# schematic.net
KiCad netlist of a schematic drawn in EAGLE
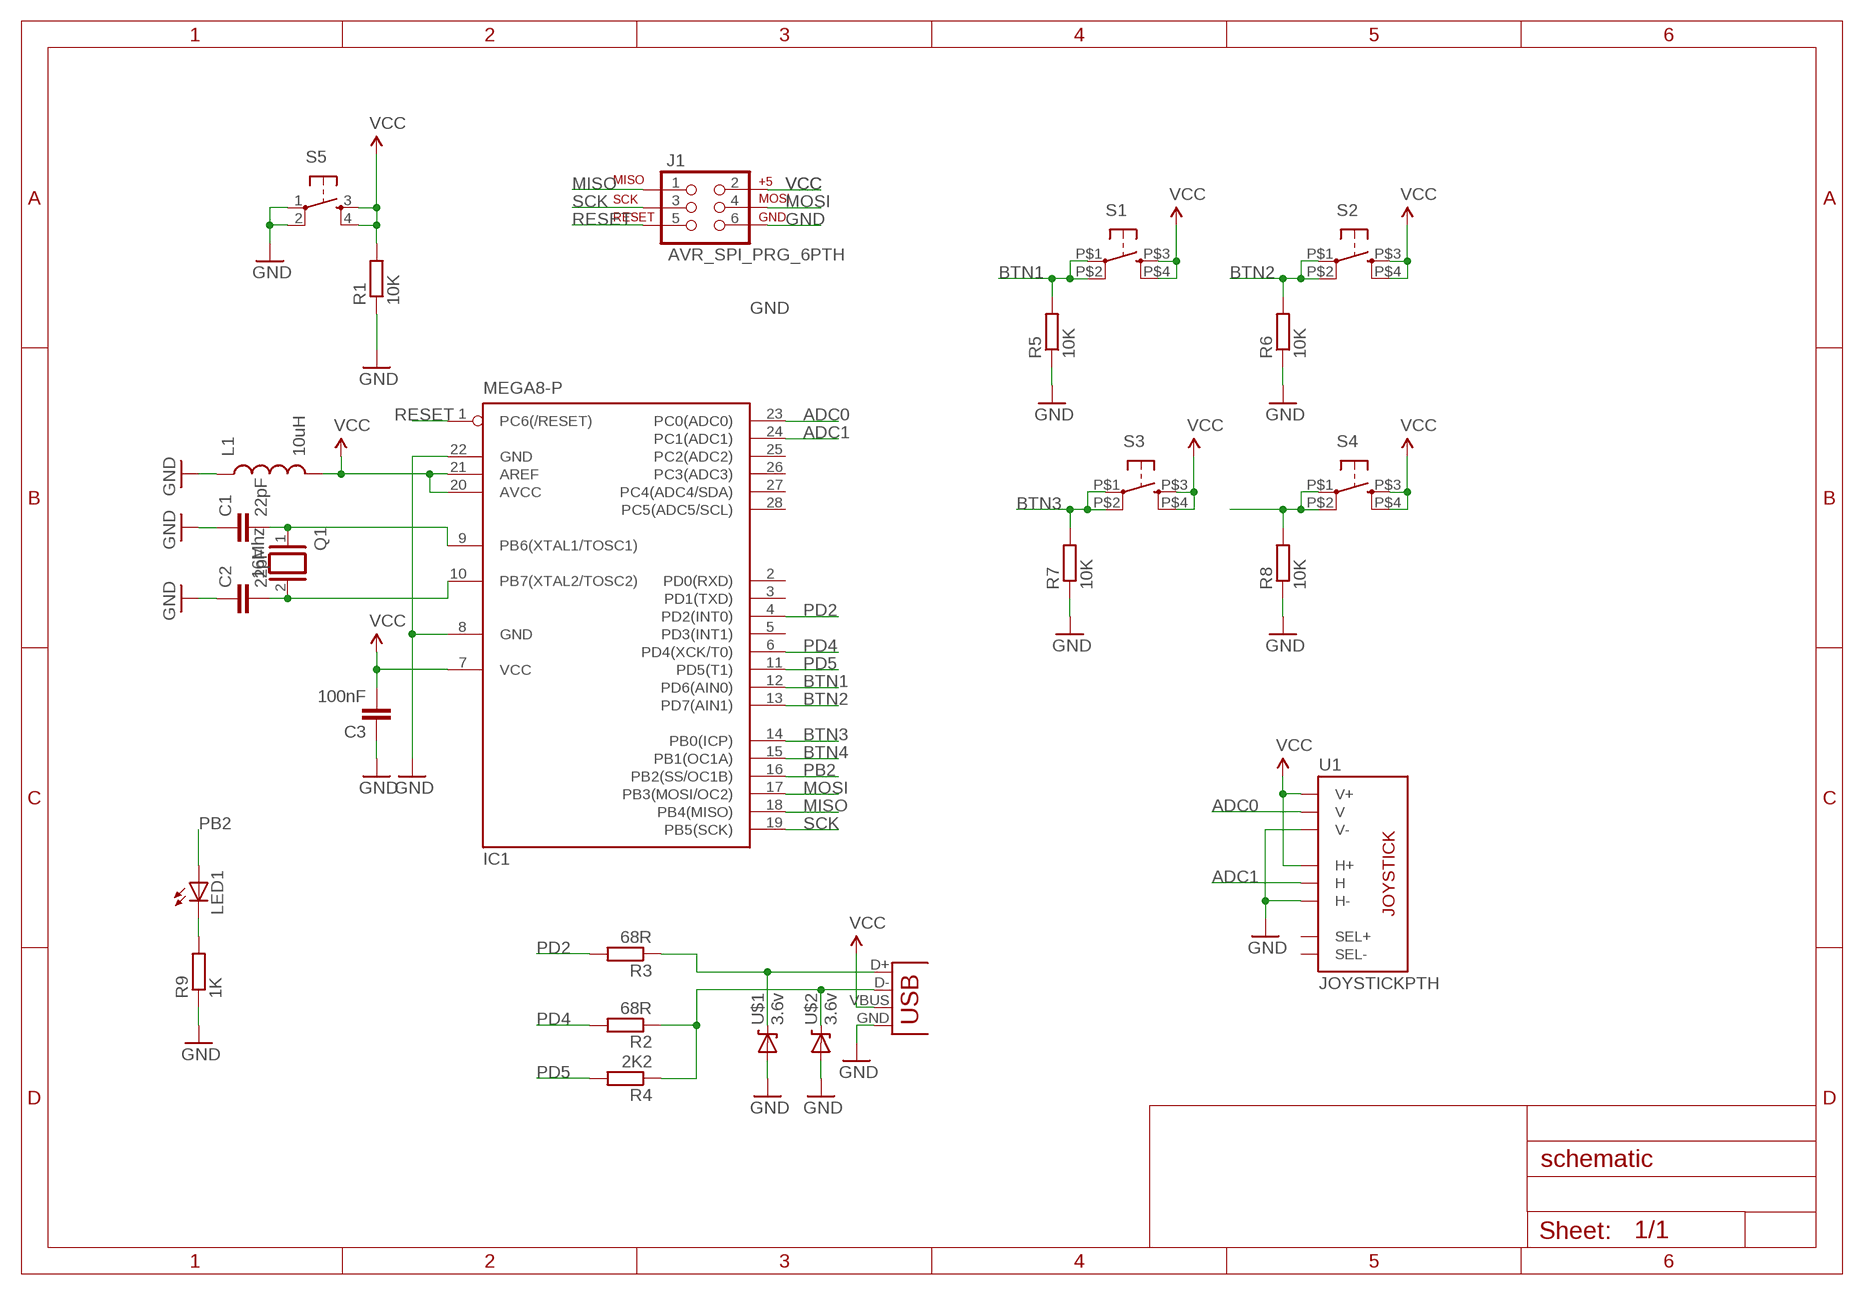
[diagram p0: schematic, sheet 1]

(export (version "E")
  (design (tool "Eeschema 10.0.6"))
  (components
    (comp (ref "C1")
      (value "22pF")
      (footprint "eagle-import:CAP-PTH-SMALL-KIT")
      (libsource (lib "eagle-import") (part "CAPKIT"))
    )
    (comp (ref "C2")
      (value "22pF")
      (footprint "eagle-import:CAP-PTH-SMALL-KIT")
      (libsource (lib "eagle-import") (part "CAPKIT"))
    )
    (comp (ref "C3")
      (value "100nF")
      (footprint "eagle-import:CAP-PTH-SMALL-KIT")
      (libsource (lib "eagle-import") (part "CAPKIT"))
    )
    (comp (ref "IC1")
      (value "MEGA8-P")
      (footprint "eagle-import:DIL28-3")
      (libsource (lib "eagle-import") (part "MEGA8-P"))
    )
    (comp (ref "J1")
      (value "AVR_SPI_PRG_6PTH")
      (footprint "eagle-import:2X3")
      (libsource (lib "eagle-import") (part "AVR_SPI_PRG_6PTH"))
    )
    (comp (ref "L1")
      (value "10uH")
      (footprint "eagle-import:AXIAL-0.6")
      (libsource (lib "eagle-import") (part "INDUCTORAXIAL-0.6"))
    )
    (comp (ref "LED1")
      (value "LED3MM")
      (footprint "eagle-import:LED3MM")
      (libsource (lib "eagle-import") (part "LED3MM"))
    )
    (comp (ref "Q1")
      (value "16Mhz")
      (footprint "eagle-import:Q")
      (libsource (lib "eagle-import") (part "XTAL"))
    )
    (comp (ref "R1")
      (value "10K")
      (footprint "eagle-import:0204_7")
      (libsource (lib "eagle-import") (part "R-EU_0204/7"))
    )
    (comp (ref "R2")
      (value "68R")
      (footprint "eagle-import:0204_7")
      (libsource (lib "eagle-import") (part "R-EU_0204/7"))
    )
    (comp (ref "R3")
      (value "68R")
      (footprint "eagle-import:0204_7")
      (libsource (lib "eagle-import") (part "R-EU_0204/7"))
    )
    (comp (ref "R4")
      (value "2K2")
      (footprint "eagle-import:0204_7")
      (libsource (lib "eagle-import") (part "R-EU_0204/7"))
    )
    (comp (ref "R5")
      (value "10K")
      (footprint "eagle-import:0204_7")
      (libsource (lib "eagle-import") (part "R-EU_0204/7"))
    )
    (comp (ref "R6")
      (value "10K")
      (footprint "eagle-import:0204_7")
      (libsource (lib "eagle-import") (part "R-EU_0204/7"))
    )
    (comp (ref "R7")
      (value "10K")
      (footprint "eagle-import:0204_7")
      (libsource (lib "eagle-import") (part "R-EU_0204/7"))
    )
    (comp (ref "R8")
      (value "10K")
      (footprint "eagle-import:0204_7")
      (libsource (lib "eagle-import") (part "R-EU_0204/7"))
    )
    (comp (ref "R9")
      (value "1K")
      (footprint "eagle-import:0204_7")
      (libsource (lib "eagle-import") (part "R-EU_0204/7"))
    )
    (comp (ref "S1")
      (value "TAC_SWITCHKSA_SEALED")
      (footprint "eagle-import:KSA_SEALED_TAC_SWITCH")
      (libsource (lib "eagle-import") (part "TAC_SWITCHKSA_SEALED"))
    )
    (comp (ref "S2")
      (value "TAC_SWITCHKSA_SEALED")
      (footprint "eagle-import:KSA_SEALED_TAC_SWITCH")
      (libsource (lib "eagle-import") (part "TAC_SWITCHKSA_SEALED"))
    )
    (comp (ref "S3")
      (value "TAC_SWITCHKSA_SEALED")
      (footprint "eagle-import:KSA_SEALED_TAC_SWITCH")
      (libsource (lib "eagle-import") (part "TAC_SWITCHKSA_SEALED"))
    )
    (comp (ref "S4")
      (value "TAC_SWITCHKSA_SEALED")
      (footprint "eagle-import:KSA_SEALED_TAC_SWITCH")
      (libsource (lib "eagle-import") (part "TAC_SWITCHKSA_SEALED"))
    )
    (comp (ref "S5")
      (value "TAC_SWITCHPTH")
      (footprint "eagle-import:TACTILE-PTH")
      (libsource (lib "eagle-import") (part "TAC_SWITCHPTH"))
    )
    (comp (ref "U$1")
      (value "3.6v")
      (footprint "eagle-import:DIODE-ZENER")
      (libsource (lib "eagle-import") (part "DIODE-ZENERPTH"))
    )
    (comp (ref "U$2")
      (value "3.6v")
      (footprint "eagle-import:DIODE-ZENER")
      (libsource (lib "eagle-import") (part "DIODE-ZENERPTH"))
    )
    (comp (ref "U1")
      (value "JOYSTICKPTH")
      (footprint "eagle-import:JOYSTICK")
      (libsource (lib "eagle-import") (part "JOYSTICKPTH"))
    )
    (comp (ref "X1")
      (value "USBPTH-VERTICAL")
      (footprint "eagle-import:USB-B-PTH-VERTICAL")
      (libsource (lib "eagle-import") (part "USBPTH-VERTICAL"))
    )
  )
  (nets
    (net (code "1") (name "/ADC0") (class "Default")
      (node (ref "IC1") (pin "23") (pinfunction "PC0(ADC0)_23") (pintype "bidirectional"))
      (node (ref "U1") (pin "V2") (pinfunction "V_V2") (pintype "bidirectional"))
    )
    (net (code "2") (name "/ADC1") (class "Default")
      (node (ref "IC1") (pin "24") (pinfunction "PC1(ADC1)_24") (pintype "bidirectional"))
      (node (ref "U1") (pin "H2") (pinfunction "H_H2") (pintype "bidirectional"))
    )
    (net (code "3") (name "/BTN1") (class "Default")
      (node (ref "IC1") (pin "12") (pinfunction "PD6(AIN0)_12") (pintype "bidirectional"))
      (node (ref "R5") (pin "2") (pinfunction "2_2") (pintype "passive"))
      (node (ref "S1") (pin "P$1") (pinfunction "1_P$1") (pintype "passive"))
      (node (ref "S1") (pin "P$2") (pinfunction "2_P$2") (pintype "passive"))
    )
    (net (code "4") (name "/BTN2") (class "Default")
      (node (ref "IC1") (pin "13") (pinfunction "PD7(AIN1)_13") (pintype "bidirectional"))
      (node (ref "R6") (pin "2") (pinfunction "2_2") (pintype "passive"))
      (node (ref "S2") (pin "P$1") (pinfunction "1_P$1") (pintype "passive"))
      (node (ref "S2") (pin "P$2") (pinfunction "2_P$2") (pintype "passive"))
    )
    (net (code "5") (name "/BTN3") (class "Default")
      (node (ref "IC1") (pin "14") (pinfunction "PB0(ICP)_14") (pintype "bidirectional"))
      (node (ref "R7") (pin "2") (pinfunction "2_2") (pintype "passive"))
      (node (ref "S3") (pin "P$1") (pinfunction "1_P$1") (pintype "passive"))
      (node (ref "S3") (pin "P$2") (pinfunction "2_P$2") (pintype "passive"))
    )
    (net (code "6") (name "/BTN4") (class "Default")
      (node (ref "IC1") (pin "15") (pinfunction "PB1(OC1A)_15") (pintype "bidirectional"))
      (node (ref "R8") (pin "2") (pinfunction "2_2") (pintype "passive"))
      (node (ref "S4") (pin "P$1") (pinfunction "1_P$1") (pintype "passive"))
      (node (ref "S4") (pin "P$2") (pinfunction "2_P$2") (pintype "passive"))
    )
    (net (code "7") (name "/MISO") (class "Default")
      (node (ref "IC1") (pin "18") (pinfunction "PB4(MISO)_18") (pintype "bidirectional"))
      (node (ref "J1") (pin "1") (pinfunction "1_1") (pintype "passive"))
    )
    (net (code "8") (name "/MOSI") (class "Default")
      (node (ref "IC1") (pin "17") (pinfunction "PB3(MOSI/OC2)_17") (pintype "bidirectional"))
      (node (ref "J1") (pin "4") (pinfunction "4_4") (pintype "passive"))
    )
    (net (code "9") (name "/PB2") (class "Default")
      (node (ref "IC1") (pin "16") (pinfunction "PB2(SS/OC1B)_16") (pintype "bidirectional"))
      (node (ref "LED1") (pin "A") (pinfunction "A_A") (pintype "passive"))
    )
    (net (code "10") (name "/PD2") (class "Default")
      (node (ref "IC1") (pin "4") (pinfunction "PD2(INT0)_4") (pintype "bidirectional"))
      (node (ref "R3") (pin "2") (pinfunction "2_2") (pintype "passive"))
    )
    (net (code "11") (name "/PD4") (class "Default")
      (node (ref "IC1") (pin "6") (pinfunction "PD4(XCK/T0)_6") (pintype "bidirectional"))
      (node (ref "R2") (pin "2") (pinfunction "2_2") (pintype "passive"))
    )
    (net (code "12") (name "/PD5") (class "Default")
      (node (ref "IC1") (pin "11") (pinfunction "PD5(T1)_11") (pintype "bidirectional"))
      (node (ref "R4") (pin "2") (pinfunction "2_2") (pintype "passive"))
    )
    (net (code "13") (name "/RESET") (class "Default")
      (node (ref "IC1") (pin "1") (pinfunction "PC6(/RESET)_1") (pintype "bidirectional"))
      (node (ref "J1") (pin "5") (pinfunction "5_5") (pintype "passive"))
    )
    (net (code "14") (name "/SCK") (class "Default")
      (node (ref "IC1") (pin "19") (pinfunction "PB5(SCK)_19") (pintype "bidirectional"))
      (node (ref "J1") (pin "3") (pinfunction "3_3") (pintype "passive"))
    )
    (net (code "15") (name "GND") (class "Default")
      (node (ref "C1") (pin "1") (pinfunction "1_1") (pintype "passive"))
      (node (ref "C2") (pin "1") (pinfunction "1_1") (pintype "passive"))
      (node (ref "C3") (pin "1") (pinfunction "1_1") (pintype "passive"))
      (node (ref "IC1") (pin "22") (pinfunction "GND_22") (pintype "power_in"))
      (node (ref "IC1") (pin "8") (pinfunction "GND_8") (pintype "power_in"))
      (node (ref "J1") (pin "6") (pinfunction "6_6") (pintype "passive"))
      (node (ref "L1") (pin "P$1") (pinfunction "1_P$1") (pintype "passive"))
      (node (ref "R1") (pin "1") (pinfunction "1_1") (pintype "passive"))
      (node (ref "R5") (pin "1") (pinfunction "1_1") (pintype "passive"))
      (node (ref "R6") (pin "1") (pinfunction "1_1") (pintype "passive"))
      (node (ref "R7") (pin "1") (pinfunction "1_1") (pintype "passive"))
      (node (ref "R8") (pin "1") (pinfunction "1_1") (pintype "passive"))
      (node (ref "R9") (pin "1") (pinfunction "1_1") (pintype "passive"))
      (node (ref "S5") (pin "1") (pinfunction "1_1") (pintype "passive"))
      (node (ref "S5") (pin "2") (pinfunction "2_2") (pintype "passive"))
      (node (ref "U$1") (pin "P$2") (pinfunction "A_P$2") (pintype "passive"))
      (node (ref "U$2") (pin "P$2") (pinfunction "A_P$2") (pintype "passive"))
      (node (ref "U1") (pin "H3") (pinfunction "H-_H3") (pintype "bidirectional"))
      (node (ref "U1") (pin "V3") (pinfunction "V-_V3") (pintype "bidirectional"))
      (node (ref "X1") (pin "GND") (pinfunction "GND_GND") (pintype "bidirectional"))
    )
    (net (code "16") (name "Net-(IC1-PB6(XTAL1{slash}TOSC1))") (class "Default")
      (node (ref "C1") (pin "2") (pinfunction "2_2") (pintype "passive"))
      (node (ref "IC1") (pin "9") (pinfunction "PB6(XTAL1/TOSC1)_9") (pintype "bidirectional"))
      (node (ref "Q1") (pin "1") (pinfunction "1_1") (pintype "passive"))
    )
    (net (code "17") (name "Net-(IC1-PB7(XTAL2{slash}TOSC2))") (class "Default")
      (node (ref "C2") (pin "2") (pinfunction "2_2") (pintype "passive"))
      (node (ref "IC1") (pin "10") (pinfunction "PB7(XTAL2/TOSC2)_10") (pintype "bidirectional"))
      (node (ref "Q1") (pin "2") (pinfunction "2_2") (pintype "passive"))
    )
    (net (code "18") (name "Net-(LED1-C)") (class "Default")
      (node (ref "LED1") (pin "K") (pinfunction "C_K") (pintype "passive"))
      (node (ref "R9") (pin "2") (pinfunction "2_2") (pintype "passive"))
    )
    (net (code "19") (name "Net-(U$1-C)") (class "Default")
      (node (ref "R3") (pin "1") (pinfunction "1_1") (pintype "passive"))
      (node (ref "U$1") (pin "P$1") (pinfunction "C_P$1") (pintype "passive"))
      (node (ref "X1") (pin "D+") (pinfunction "D+_D+") (pintype "bidirectional"))
    )
    (net (code "20") (name "Net-(U$2-C)") (class "Default")
      (node (ref "R2") (pin "1") (pinfunction "1_1") (pintype "passive"))
      (node (ref "R4") (pin "1") (pinfunction "1_1") (pintype "passive"))
      (node (ref "U$2") (pin "P$1") (pinfunction "C_P$1") (pintype "passive"))
      (node (ref "X1") (pin "D-") (pinfunction "D-_D-") (pintype "bidirectional"))
    )
    (net (code "21") (name "VCC") (class "Default")
      (node (ref "C3") (pin "2") (pinfunction "2_2") (pintype "passive"))
      (node (ref "IC1") (pin "20") (pinfunction "AVCC_20") (pintype "power_in"))
      (node (ref "IC1") (pin "21") (pinfunction "AREF_21") (pintype "passive"))
      (node (ref "IC1") (pin "7") (pinfunction "VCC_7") (pintype "power_in"))
      (node (ref "J1") (pin "2") (pinfunction "2_2") (pintype "passive"))
      (node (ref "L1") (pin "P$2") (pinfunction "2_P$2") (pintype "passive"))
      (node (ref "R1") (pin "2") (pinfunction "2_2") (pintype "passive"))
      (node (ref "S1") (pin "P$3") (pinfunction "3_P$3") (pintype "passive"))
      (node (ref "S1") (pin "P$4") (pinfunction "4_P$4") (pintype "passive"))
      (node (ref "S2") (pin "P$3") (pinfunction "3_P$3") (pintype "passive"))
      (node (ref "S2") (pin "P$4") (pinfunction "4_P$4") (pintype "passive"))
      (node (ref "S3") (pin "P$3") (pinfunction "3_P$3") (pintype "passive"))
      (node (ref "S3") (pin "P$4") (pinfunction "4_P$4") (pintype "passive"))
      (node (ref "S4") (pin "P$3") (pinfunction "3_P$3") (pintype "passive"))
      (node (ref "S4") (pin "P$4") (pinfunction "4_P$4") (pintype "passive"))
      (node (ref "S5") (pin "3") (pinfunction "3_3") (pintype "passive"))
      (node (ref "S5") (pin "4") (pinfunction "4_4") (pintype "passive"))
      (node (ref "U1") (pin "H1") (pinfunction "H+_H1") (pintype "bidirectional"))
      (node (ref "U1") (pin "V1") (pinfunction "V+_V1") (pintype "bidirectional"))
      (node (ref "X1") (pin "VBUS") (pinfunction "VBUS_VBUS") (pintype "bidirectional"))
    )
    (net (code "22") (name "unconnected-(IC1-PC2(ADC2)-Pad25)") (class "Default")
      (node (ref "IC1") (pin "25") (pinfunction "PC2(ADC2)_25") (pintype "bidirectional"))
    )
    (net (code "23") (name "unconnected-(IC1-PC3(ADC3)-Pad26)") (class "Default")
      (node (ref "IC1") (pin "26") (pinfunction "PC3(ADC3)_26") (pintype "bidirectional"))
    )
    (net (code "24") (name "unconnected-(IC1-PC4(ADC4{slash}SDA)-Pad27)") (class "Default")
      (node (ref "IC1") (pin "27") (pinfunction "PC4(ADC4/SDA)_27") (pintype "bidirectional"))
    )
    (net (code "25") (name "unconnected-(IC1-PC5(ADC5{slash}SCL)-Pad28)") (class "Default")
      (node (ref "IC1") (pin "28") (pinfunction "PC5(ADC5/SCL)_28") (pintype "bidirectional"))
    )
    (net (code "26") (name "unconnected-(IC1-PD0(RXD)-Pad2)") (class "Default")
      (node (ref "IC1") (pin "2") (pinfunction "PD0(RXD)_2") (pintype "bidirectional"))
    )
    (net (code "27") (name "unconnected-(IC1-PD1(TXD)-Pad3)") (class "Default")
      (node (ref "IC1") (pin "3") (pinfunction "PD1(TXD)_3") (pintype "bidirectional"))
    )
    (net (code "28") (name "unconnected-(IC1-PD3(INT1)-Pad5)") (class "Default")
      (node (ref "IC1") (pin "5") (pinfunction "PD3(INT1)_5") (pintype "bidirectional"))
    )
    (net (code "29") (name "unconnected-(U1-SEL+-PadB1A)") (class "Default")
      (node (ref "U1") (pin "B1A") (pinfunction "SEL+_B1A") (pintype "bidirectional"))
    )
    (net (code "30") (name "unconnected-(U1-SEL--PadB2A)") (class "Default")
      (node (ref "U1") (pin "B2A") (pinfunction "SEL-_B2A") (pintype "bidirectional"))
    )
  )
)
